# 14_HD4_PUMP.net
KiCad netlist of a schematic drawn in Altium Designer
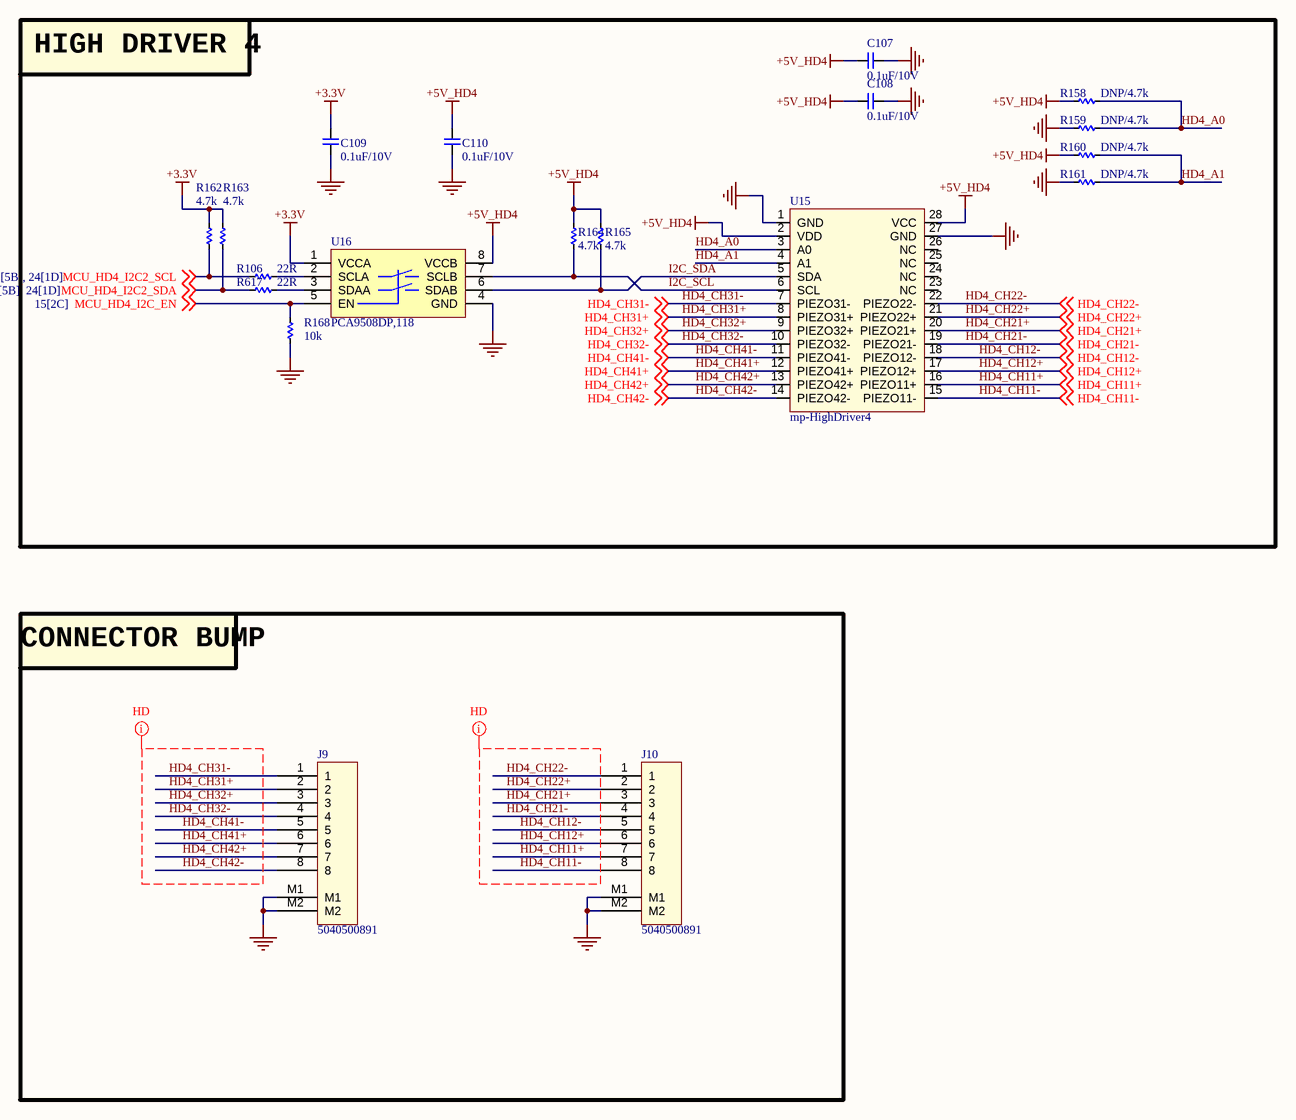
[diagram p0: 14_HD4_PUMP.SchDoc]

(export (version "E")
  (design (tool "Eeschema 10.0.6"))
  (components
    (comp (ref "C107")
      (value "0.1uF/10V")
      (footprint "CAP_C_1005X60")
      (description "CAP CHIP")
      (libsource (lib "LABLIB") (part "_CAP_C_2"))
    )
    (comp (ref "C108")
      (value "0.1uF/10V")
      (footprint "CAP_C_1005X60")
      (description "CAP CHIP")
      (libsource (lib "LABLIB") (part "_CAP_C_2"))
    )
    (comp (ref "C109")
      (value "0.1uF/10V")
      (footprint "CAP_C_1005X60")
      (description "CAP CHIP")
      (libsource (lib "LABLIB") (part "_CAP_C_2"))
    )
    (comp (ref "C110")
      (value "0.1uF/10V")
      (footprint "CAP_C_1005X60")
      (description "CAP CHIP")
      (libsource (lib "LABLIB") (part "_CAP_C_2"))
    )
    (comp (ref "J9")
      (value "5040500891")
      (footprint "MOLEX_5040500891")
      (libsource (lib "LABLIB") (part "Header 8x1_2M"))
    )
    (comp (ref "J10")
      (value "5040500891")
      (footprint "MOLEX_5040500891")
      (libsource (lib "LABLIB") (part "Header 8x1_2M"))
    )
    (comp (ref "R106")
      (value "22R")
      (footprint "RES_C_1005X40")
      (description "RES")
      (libsource (lib "LABLIB") (part "_RES_B_2"))
    )
    (comp (ref "R158")
      (value "DNP/4.7k")
      (footprint "RES_C_1005X40")
      (description "RES")
      (libsource (lib "LABLIB") (part "_RES_B_2"))
    )
    (comp (ref "R159")
      (value "DNP/4.7k")
      (footprint "RES_C_1005X40")
      (description "RES")
      (libsource (lib "LABLIB") (part "_RES_B_2"))
    )
    (comp (ref "R160")
      (value "DNP/4.7k")
      (footprint "RES_C_1005X40")
      (description "RES")
      (libsource (lib "LABLIB") (part "_RES_B_2"))
    )
    (comp (ref "R161")
      (value "DNP/4.7k")
      (footprint "RES_C_1005X40")
      (description "RES")
      (libsource (lib "LABLIB") (part "_RES_B_2"))
    )
    (comp (ref "R162")
      (value "4.7k")
      (footprint "RES_C_1005X40")
      (description "RES")
      (libsource (lib "LABLIB") (part "_RES_B_2"))
    )
    (comp (ref "R163")
      (value "4.7k")
      (footprint "RES_C_1005X40")
      (description "RES")
      (libsource (lib "LABLIB") (part "_RES_B_2"))
    )
    (comp (ref "R164")
      (value "4.7k")
      (footprint "RES_C_1005X40")
      (description "RES")
      (libsource (lib "LABLIB") (part "_RES_B_2"))
    )
    (comp (ref "R165")
      (value "4.7k")
      (footprint "RES_C_1005X40")
      (description "RES")
      (libsource (lib "LABLIB") (part "_RES_B_2"))
    )
    (comp (ref "R168")
      (value "10k")
      (footprint "RES_C_1005X40")
      (description "RES")
      (libsource (lib "LABLIB") (part "_RES_B_2"))
    )
    (comp (ref "R617")
      (value "22R")
      (footprint "RES_C_1005X40")
      (description "RES")
      (libsource (lib "LABLIB") (part "_RES_B_2"))
    )
    (comp (ref "U15")
      (value "mp-HighDriver4")
      (footprint "MP_HIGHDRIVER4")
      (libsource (lib "new_component") (part "mp_HighDriver4"))
    )
    (comp (ref "U16")
      (value "PCA9508DP,118")
      (footprint "TSOP8")
      (libsource (lib "EXP_HW_V3") (part "PCA9508DP,118"))
    )
  )
  (nets
    (net (code "1") (name "+3.3V") (class "Default")
      (node (ref "C109") (pin "2") (pinfunction "2_2") (pintype "passive"))
      (node (ref "R162") (pin "1") (pinfunction "1_1") (pintype "passive"))
      (node (ref "R163") (pin "1") (pinfunction "1_1") (pintype "passive"))
      (node (ref "U16") (pin "1") (pinfunction "VCCA_1") (pintype "passive"))
    )
    (net (code "2") (name "+5V_HD4") (class "Default")
      (node (ref "C107") (pin "2") (pinfunction "2_2") (pintype "passive"))
      (node (ref "C108") (pin "2") (pinfunction "2_2") (pintype "passive"))
      (node (ref "C110") (pin "2") (pinfunction "2_2") (pintype "passive"))
      (node (ref "R158") (pin "1") (pinfunction "1_1") (pintype "passive"))
      (node (ref "R160") (pin "1") (pinfunction "1_1") (pintype "passive"))
      (node (ref "R164") (pin "1") (pinfunction "1_1") (pintype "passive"))
      (node (ref "R165") (pin "1") (pinfunction "1_1") (pintype "passive"))
      (node (ref "U15") (pin "2") (pinfunction "VDD_2") (pintype "power_in"))
      (node (ref "U15") (pin "28") (pinfunction "VCC_28") (pintype "power_in"))
      (node (ref "U16") (pin "8") (pinfunction "VCCB_8") (pintype "passive"))
    )
    (net (code "3") (name "/HD4_A0") (class "Default")
      (node (ref "R158") (pin "2") (pinfunction "2_2") (pintype "passive"))
      (node (ref "R159") (pin "2") (pinfunction "2_2") (pintype "passive"))
      (node (ref "U15") (pin "3") (pinfunction "A0_3") (pintype "passive"))
    )
    (net (code "4") (name "/HD4_A1") (class "Default")
      (node (ref "R160") (pin "2") (pinfunction "2_2") (pintype "passive"))
      (node (ref "R161") (pin "2") (pinfunction "2_2") (pintype "passive"))
      (node (ref "U15") (pin "4") (pinfunction "A1_4") (pintype "passive"))
    )
    (net (code "5") (name "/I2C_SCL") (class "Default")
      (node (ref "R164") (pin "2") (pinfunction "2_2") (pintype "passive"))
      (node (ref "U15") (pin "6") (pinfunction "SCL_6") (pintype "passive"))
      (node (ref "U16") (pin "7") (pinfunction "SCLB_7") (pintype "passive"))
    )
    (net (code "6") (name "/I2C_SDA") (class "Default")
      (node (ref "R165") (pin "2") (pinfunction "2_2") (pintype "passive"))
      (node (ref "U15") (pin "5") (pinfunction "SDA_5") (pintype "passive"))
      (node (ref "U16") (pin "6") (pinfunction "SDAB_6") (pintype "passive"))
    )
    (net (code "7") (name "GND") (class "Default")
      (node (ref "C107") (pin "1") (pinfunction "1_1") (pintype "passive"))
      (node (ref "C108") (pin "1") (pinfunction "1_1") (pintype "passive"))
      (node (ref "C109") (pin "1") (pinfunction "1_1") (pintype "passive"))
      (node (ref "C110") (pin "1") (pinfunction "1_1") (pintype "passive"))
      (node (ref "J10") (pin "M1") (pinfunction "M1_M1") (pintype "passive"))
      (node (ref "J10") (pin "M2") (pinfunction "M2_M2") (pintype "passive"))
      (node (ref "J9") (pin "M1") (pinfunction "M1_M1") (pintype "passive"))
      (node (ref "J9") (pin "M2") (pinfunction "M2_M2") (pintype "passive"))
      (node (ref "R159") (pin "1") (pinfunction "1_1") (pintype "passive"))
      (node (ref "R161") (pin "1") (pinfunction "1_1") (pintype "passive"))
      (node (ref "R168") (pin "2") (pinfunction "2_2") (pintype "passive"))
      (node (ref "U15") (pin "1") (pinfunction "GND_1") (pintype "power_in"))
      (node (ref "U15") (pin "27") (pinfunction "GND_27") (pintype "power_in"))
      (node (ref "U16") (pin "4") (pinfunction "GND_4") (pintype "passive"))
    )
    (net (code "8") (name "HD4_CH11+") (class "Default")
      (node (ref "J10") (pin "7") (pinfunction "7_7") (pintype "passive"))
      (node (ref "U15") (pin "16") (pinfunction "PIEZO11+_16") (pintype "passive"))
    )
    (net (code "9") (name "HD4_CH11-") (class "Default")
      (node (ref "J10") (pin "8") (pinfunction "8_8") (pintype "passive"))
      (node (ref "U15") (pin "15") (pinfunction "PIEZO11-_15") (pintype "passive"))
    )
    (net (code "10") (name "HD4_CH12+") (class "Default")
      (node (ref "J10") (pin "6") (pinfunction "6_6") (pintype "passive"))
      (node (ref "U15") (pin "17") (pinfunction "PIEZO12+_17") (pintype "passive"))
    )
    (net (code "11") (name "HD4_CH12-") (class "Default")
      (node (ref "J10") (pin "5") (pinfunction "5_5") (pintype "passive"))
      (node (ref "U15") (pin "18") (pinfunction "PIEZO12-_18") (pintype "passive"))
    )
    (net (code "12") (name "HD4_CH21+") (class "Default")
      (node (ref "J10") (pin "3") (pinfunction "3_3") (pintype "passive"))
      (node (ref "U15") (pin "20") (pinfunction "PIEZO21+_20") (pintype "passive"))
    )
    (net (code "13") (name "HD4_CH21-") (class "Default")
      (node (ref "J10") (pin "4") (pinfunction "4_4") (pintype "passive"))
      (node (ref "U15") (pin "19") (pinfunction "PIEZO21-_19") (pintype "passive"))
    )
    (net (code "14") (name "HD4_CH22+") (class "Default")
      (node (ref "J10") (pin "2") (pinfunction "2_2") (pintype "passive"))
      (node (ref "U15") (pin "21") (pinfunction "PIEZO22+_21") (pintype "passive"))
    )
    (net (code "15") (name "HD4_CH22-") (class "Default")
      (node (ref "J10") (pin "1") (pinfunction "1_1") (pintype "passive"))
      (node (ref "U15") (pin "22") (pinfunction "PIEZO22-_22") (pintype "passive"))
    )
    (net (code "16") (name "HD4_CH31+") (class "Default")
      (node (ref "J9") (pin "2") (pinfunction "2_2") (pintype "passive"))
      (node (ref "U15") (pin "8") (pinfunction "PIEZO31+_8") (pintype "passive"))
    )
    (net (code "17") (name "HD4_CH31-") (class "Default")
      (node (ref "J9") (pin "1") (pinfunction "1_1") (pintype "passive"))
      (node (ref "U15") (pin "7") (pinfunction "PIEZO31-_7") (pintype "passive"))
    )
    (net (code "18") (name "HD4_CH32+") (class "Default")
      (node (ref "J9") (pin "3") (pinfunction "3_3") (pintype "passive"))
      (node (ref "U15") (pin "9") (pinfunction "PIEZO32+_9") (pintype "passive"))
    )
    (net (code "19") (name "HD4_CH32-") (class "Default")
      (node (ref "J9") (pin "4") (pinfunction "4_4") (pintype "passive"))
      (node (ref "U15") (pin "10") (pinfunction "PIEZO32-_10") (pintype "passive"))
    )
    (net (code "20") (name "HD4_CH41+") (class "Default")
      (node (ref "J9") (pin "6") (pinfunction "6_6") (pintype "passive"))
      (node (ref "U15") (pin "12") (pinfunction "PIEZO41+_12") (pintype "passive"))
    )
    (net (code "21") (name "HD4_CH41-") (class "Default")
      (node (ref "J9") (pin "5") (pinfunction "5_5") (pintype "passive"))
      (node (ref "U15") (pin "11") (pinfunction "PIEZO41-_11") (pintype "passive"))
    )
    (net (code "22") (name "HD4_CH42+") (class "Default")
      (node (ref "J9") (pin "7") (pinfunction "7_7") (pintype "passive"))
      (node (ref "U15") (pin "13") (pinfunction "PIEZO42+_13") (pintype "passive"))
    )
    (net (code "23") (name "HD4_CH42-") (class "Default")
      (node (ref "J9") (pin "8") (pinfunction "8_8") (pintype "passive"))
      (node (ref "U15") (pin "14") (pinfunction "PIEZO42-_14") (pintype "passive"))
    )
    (net (code "24") (name "MCU_HD4_I2C2_SCL") (class "Default")
      (node (ref "R106") (pin "2") (pinfunction "2_2") (pintype "passive"))
      (node (ref "R162") (pin "2") (pinfunction "2_2") (pintype "passive"))
    )
    (net (code "25") (name "MCU_HD4_I2C2_SDA") (class "Default")
      (node (ref "R163") (pin "2") (pinfunction "2_2") (pintype "passive"))
      (node (ref "R617") (pin "2") (pinfunction "2_2") (pintype "passive"))
    )
    (net (code "26") (name "MCU_HD4_I2C_EN") (class "Default")
      (node (ref "R168") (pin "1") (pinfunction "1_1") (pintype "passive"))
      (node (ref "U16") (pin "5") (pinfunction "EN_5") (pintype "passive"))
    )
    (net (code "27") (name "Net-(U16-SCLA)") (class "Default")
      (node (ref "R106") (pin "1") (pinfunction "1_1") (pintype "passive"))
      (node (ref "U16") (pin "2") (pinfunction "SCLA_2") (pintype "passive"))
    )
    (net (code "28") (name "Net-(U16-SDAA)") (class "Default")
      (node (ref "R617") (pin "1") (pinfunction "1_1") (pintype "passive"))
      (node (ref "U16") (pin "3") (pinfunction "SDAA_3") (pintype "passive"))
    )
    (net (code "29") (name "unconnected-(U15-NC-Pad23)") (class "Default")
      (node (ref "U15") (pin "23") (pinfunction "NC_23") (pintype "passive"))
    )
    (net (code "30") (name "unconnected-(U15-NC-Pad24)") (class "Default")
      (node (ref "U15") (pin "24") (pinfunction "NC_24") (pintype "passive"))
    )
    (net (code "31") (name "unconnected-(U15-NC-Pad25)") (class "Default")
      (node (ref "U15") (pin "25") (pinfunction "NC_25") (pintype "passive"))
    )
    (net (code "32") (name "unconnected-(U15-NC-Pad26)") (class "Default")
      (node (ref "U15") (pin "26") (pinfunction "NC_26") (pintype "passive"))
    )
  )
)
